# Becca_Sap_Flow_Sensor_OG.net
KiCad netlist of a schematic drawn in EAGLE
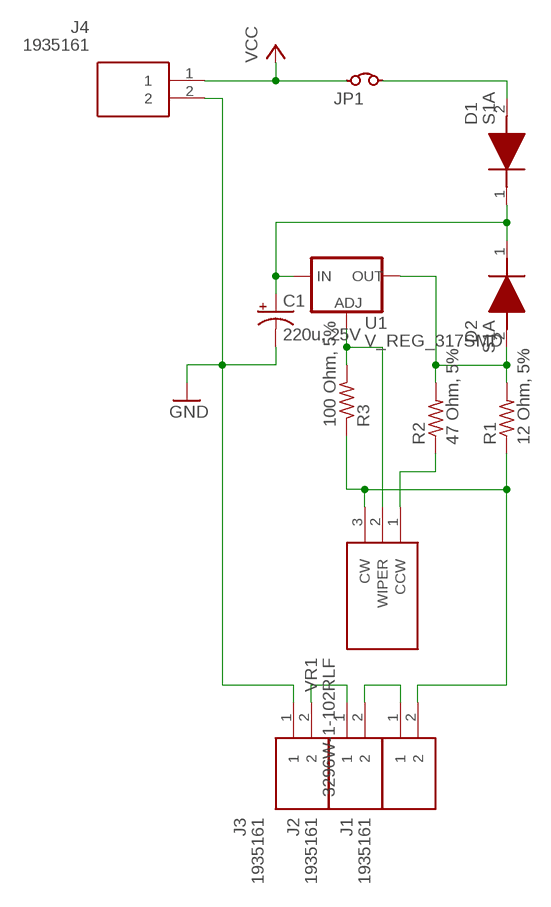
[diagram p0: schematic, sheet 1]

(export (version "E")
  (design (tool "Eeschema 10.0.6"))
  (components
    (comp (ref "C1")
      (value "220u, 25V")
      (footprint "eagle-import:PANASONIC_C")
      (libsource (lib "eagle-import") (part "CPOL-USC"))
    )
    (comp (ref "D1")
      (value "S1A")
      (footprint "eagle-import:DIOM5027X250N")
      (fields (field (name "MOUSER_PART_NUMBER") "637-S1A"))
      (libsource (lib "eagle-import") (part "S1A"))
    )
    (comp (ref "D2")
      (value "S1A")
      (footprint "eagle-import:DIOM5027X250N")
      (fields (field (name "MOUSER_PART_NUMBER") "637-S1A"))
      (libsource (lib "eagle-import") (part "S1A"))
    )
    (comp (ref "J1")
      (value "1935161")
      (footprint "eagle-import:1935161")
      (fields (field (name "MOUSER_PART_NUMBER") "651-1935161"))
      (libsource (lib "eagle-import") (part "1935161"))
    )
    (comp (ref "J2")
      (value "1935161")
      (footprint "eagle-import:1935161")
      (fields (field (name "MOUSER_PART_NUMBER") "651-1935161"))
      (libsource (lib "eagle-import") (part "1935161"))
    )
    (comp (ref "J3")
      (value "1935161")
      (footprint "eagle-import:1935161")
      (fields (field (name "MOUSER_PART_NUMBER") "651-1935161"))
      (libsource (lib "eagle-import") (part "1935161"))
    )
    (comp (ref "J4")
      (value "1935161")
      (footprint "eagle-import:1935161")
      (fields (field (name "MOUSER_PART_NUMBER") "651-1935161"))
      (libsource (lib "eagle-import") (part "1935161"))
    )
    (comp (ref "JP1")
      (value "JUMPER")
      (footprint "eagle-import:HDR2X1")
      (libsource (lib "eagle-import") (part "JUMPER"))
    )
    (comp (ref "R1")
      (value "12 Ohm, 5%")
      (footprint "eagle-import:R0805")
      (libsource (lib "eagle-import") (part "R-US_R0805"))
    )
    (comp (ref "R2")
      (value "47 Ohm, 5%")
      (footprint "eagle-import:R0805")
      (libsource (lib "eagle-import") (part "R-US_R0805"))
    )
    (comp (ref "R3")
      (value "100 Ohm, 5%")
      (footprint "eagle-import:R0805")
      (libsource (lib "eagle-import") (part "R-US_R0805"))
    )
    (comp (ref "U1")
      (value "V_REG_317SMD")
      (footprint "eagle-import:SOT223")
      (libsource (lib "eagle-import") (part "V_REG_317SMD"))
    )
    (comp (ref "VR1")
      (value "3296W-1-102RLF")
      (footprint "eagle-import:3296W1102RLF")
      (fields (field (name "MOUSER_PART_NUMBER") "652-3296W-1-102RLF"))
      (libsource (lib "eagle-import") (part "3296W-1-102RLF"))
    )
  )
  (nets
    (net (code "1") (name "GND") (class "Default")
      (node (ref "C1") (pin "-") (pinfunction "-_-") (pintype "passive"))
      (node (ref "J3") (pin "1") (pinfunction "1_1") (pintype "bidirectional"))
      (node (ref "J4") (pin "2") (pinfunction "2_2") (pintype "bidirectional"))
    )
    (net (code "2") (name "Net-(D1-A)") (class "Default")
      (node (ref "D1") (pin "2") (pinfunction "A_2") (pintype "bidirectional"))
      (node (ref "JP1") (pin "2") (pinfunction "2_2") (pintype "passive"))
    )
    (net (code "3") (name "Net-(D1-K)") (class "Default")
      (node (ref "C1") (pin "+") (pinfunction "+_+") (pintype "passive"))
      (node (ref "D1") (pin "1") (pinfunction "K_1") (pintype "bidirectional"))
      (node (ref "D2") (pin "1") (pinfunction "K_1") (pintype "bidirectional"))
      (node (ref "U1") (pin "3") (pinfunction "IN_3") (pintype "input"))
    )
    (net (code "4") (name "Net-(D2-A)") (class "Default")
      (node (ref "D2") (pin "2") (pinfunction "A_2") (pintype "bidirectional"))
      (node (ref "R1") (pin "2") (pinfunction "2_2") (pintype "passive"))
      (node (ref "R2") (pin "2") (pinfunction "2_2") (pintype "passive"))
      (node (ref "U1") (pin "2") (pinfunction "OUT_2") (pintype "output"))
    )
    (net (code "5") (name "Net-(J1-Pad1)") (class "Default")
      (node (ref "J1") (pin "1") (pinfunction "1_1") (pintype "bidirectional"))
      (node (ref "J2") (pin "2") (pinfunction "2_2") (pintype "bidirectional"))
    )
    (net (code "6") (name "Net-(J2-Pad1)") (class "Default")
      (node (ref "J2") (pin "1") (pinfunction "1_1") (pintype "bidirectional"))
      (node (ref "J3") (pin "2") (pinfunction "2_2") (pintype "bidirectional"))
    )
    (net (code "7") (name "Net-(U1-ADJ)") (class "Default")
      (node (ref "R3") (pin "2") (pinfunction "2_2") (pintype "passive"))
      (node (ref "U1") (pin "1") (pinfunction "ADJ_1") (pintype "input"))
      (node (ref "VR1") (pin "2") (pinfunction "WIPER_2") (pintype "bidirectional"))
    )
    (net (code "8") (name "Net-(VR1-CCW)") (class "Default")
      (node (ref "R2") (pin "1") (pinfunction "1_1") (pintype "passive"))
      (node (ref "VR1") (pin "1") (pinfunction "CCW_1") (pintype "bidirectional"))
    )
    (net (code "9") (name "Net-(VR1-CW)") (class "Default")
      (node (ref "J1") (pin "2") (pinfunction "2_2") (pintype "bidirectional"))
      (node (ref "R1") (pin "1") (pinfunction "1_1") (pintype "passive"))
      (node (ref "R3") (pin "1") (pinfunction "1_1") (pintype "passive"))
      (node (ref "VR1") (pin "3") (pinfunction "CW_3") (pintype "bidirectional"))
    )
    (net (code "10") (name "VCC") (class "Default")
      (node (ref "J4") (pin "1") (pinfunction "1_1") (pintype "bidirectional"))
      (node (ref "JP1") (pin "1") (pinfunction "1_1") (pintype "passive"))
    )
  )
)
